# Shield.net
KiCad netlist of a schematic drawn in EAGLE
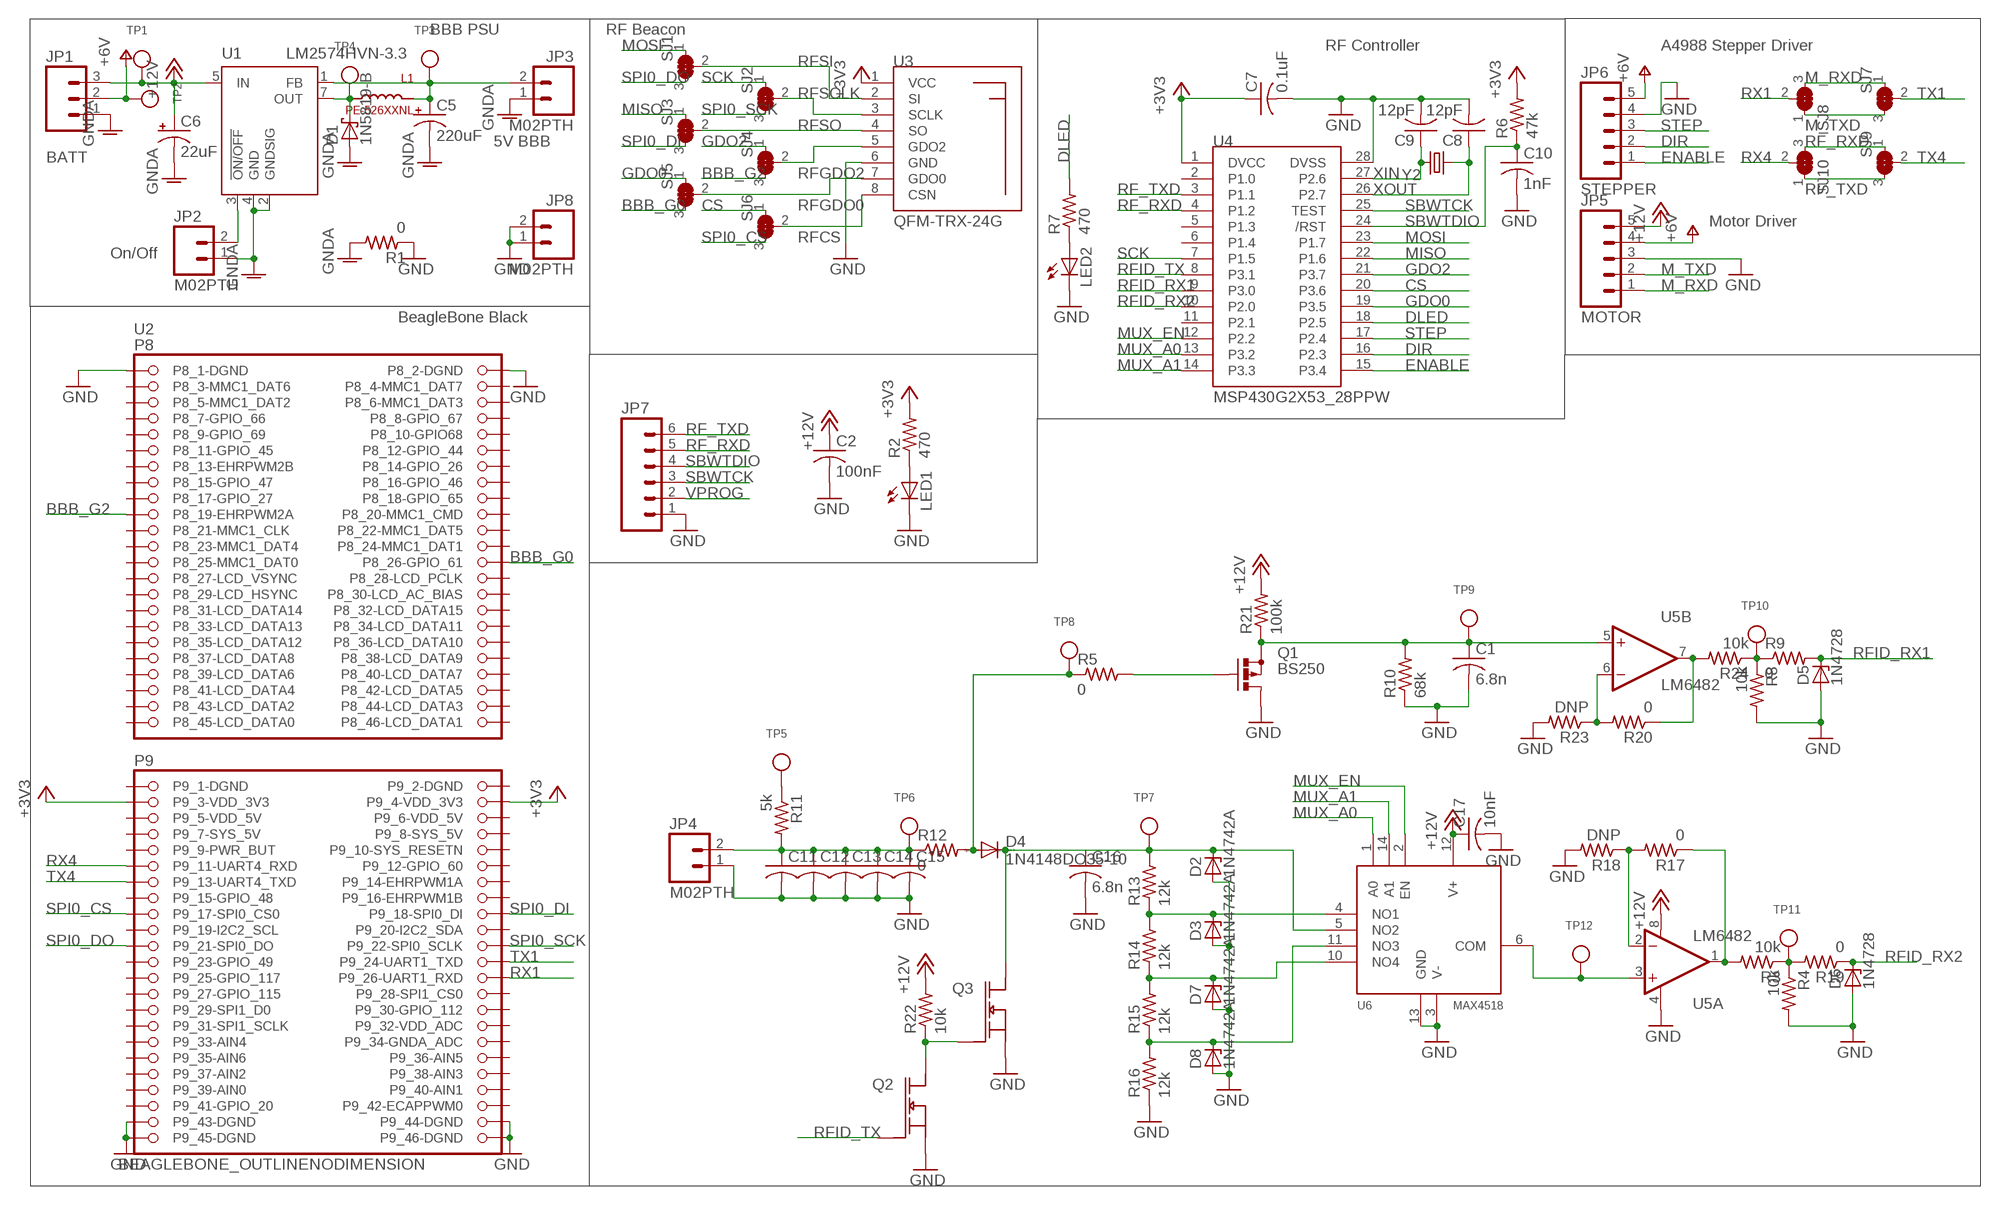
[diagram p0: schematic, sheet 1]

(export (version "E")
  (design (tool "Eeschema 10.0.6"))
  (components
    (comp (ref "C1")
      (value "6.8n")
      (footprint "eagle-import:C0805")
      (libsource (lib "eagle-import") (part "C-USC0805"))
    )
    (comp (ref "C2")
      (value "100nF")
      (footprint "eagle-import:C0805")
      (libsource (lib "eagle-import") (part "C-USC0805"))
    )
    (comp (ref "C5")
      (value "220uF")
      (footprint "eagle-import:E3,5-8")
      (libsource (lib "eagle-import") (part "CPOL-USE3.5-8"))
    )
    (comp (ref "C6")
      (value "22uF")
      (footprint "eagle-import:E2,5-5")
      (libsource (lib "eagle-import") (part "CPOL-USE2.5-5"))
    )
    (comp (ref "C7")
      (value "0.1uF")
      (footprint "eagle-import:C0805")
      (libsource (lib "eagle-import") (part "C-USC0805"))
    )
    (comp (ref "C8")
      (value "12pF")
      (footprint "eagle-import:C0805")
      (libsource (lib "eagle-import") (part "C-USC0805"))
    )
    (comp (ref "C9")
      (value "12pF")
      (footprint "eagle-import:C0805")
      (libsource (lib "eagle-import") (part "C-USC0805"))
    )
    (comp (ref "C10")
      (value "1nF")
      (footprint "eagle-import:C0805")
      (libsource (lib "eagle-import") (part "C-USC0805"))
    )
    (comp (ref "C11")
      (value "C-USC0805")
      (footprint "eagle-import:C0805")
      (libsource (lib "eagle-import") (part "C-USC0805"))
    )
    (comp (ref "C12")
      (value "C-USC0805")
      (footprint "eagle-import:C0805")
      (libsource (lib "eagle-import") (part "C-USC0805"))
    )
    (comp (ref "C13")
      (value "C-USC0805")
      (footprint "eagle-import:C0805")
      (libsource (lib "eagle-import") (part "C-USC0805"))
    )
    (comp (ref "C14")
      (value "C-USC0805")
      (footprint "eagle-import:C0805")
      (libsource (lib "eagle-import") (part "C-USC0805"))
    )
    (comp (ref "C15")
      (value "C-USC0805")
      (footprint "eagle-import:C0805")
      (libsource (lib "eagle-import") (part "C-USC0805"))
    )
    (comp (ref "C16")
      (value "6.8n")
      (footprint "eagle-import:C0805")
      (libsource (lib "eagle-import") (part "C-USC0805"))
    )
    (comp (ref "C17")
      (value "10nF")
      (footprint "eagle-import:C0805")
      (libsource (lib "eagle-import") (part "C-USC0805"))
    )
    (comp (ref "D1")
      (value "1N5819-B")
      (footprint "eagle-import:DO41-7.6")
      (libsource (lib "eagle-import") (part "1N5819-B"))
    )
    (comp (ref "D2")
      (value "1N4742A")
      (footprint "eagle-import:DO41Z10")
      (libsource (lib "eagle-import") (part "1N4728"))
    )
    (comp (ref "D3")
      (value "1N4742A")
      (footprint "eagle-import:DO41Z10")
      (libsource (lib "eagle-import") (part "1N4728"))
    )
    (comp (ref "D4")
      (value "1N4148DO35-10")
      (footprint "eagle-import:DO35-10")
      (libsource (lib "eagle-import") (part "1N4148DO35-10"))
    )
    (comp (ref "D5")
      (value "1N4728")
      (footprint "eagle-import:DO41Z10")
      (libsource (lib "eagle-import") (part "1N4728"))
    )
    (comp (ref "D6")
      (value "1N4728")
      (footprint "eagle-import:DO41Z10")
      (libsource (lib "eagle-import") (part "1N4728"))
    )
    (comp (ref "D7")
      (value "1N4742A")
      (footprint "eagle-import:DO41Z10")
      (libsource (lib "eagle-import") (part "1N4728"))
    )
    (comp (ref "D8")
      (value "1N4742A")
      (footprint "eagle-import:DO41Z10")
      (libsource (lib "eagle-import") (part "1N4728"))
    )
    (comp (ref "JP1")
      (value "M03PTH")
      (footprint "eagle-import:1X03")
      (libsource (lib "eagle-import") (part "M03PTH"))
    )
    (comp (ref "JP2")
      (value "M02PTH")
      (footprint "eagle-import:1X02")
      (libsource (lib "eagle-import") (part "M02PTH"))
    )
    (comp (ref "JP3")
      (value "M02PTH")
      (footprint "eagle-import:1X02")
      (libsource (lib "eagle-import") (part "M02PTH"))
    )
    (comp (ref "JP4")
      (value "M02PTH")
      (footprint "eagle-import:1X02")
      (libsource (lib "eagle-import") (part "M02PTH"))
    )
    (comp (ref "JP5")
      (value "MOTOR")
      (footprint "eagle-import:1X05")
      (libsource (lib "eagle-import") (part "M05PTH"))
    )
    (comp (ref "JP6")
      (value "STEPPER")
      (footprint "eagle-import:1X05")
      (libsource (lib "eagle-import") (part "M05PTH"))
    )
    (comp (ref "JP7")
      (value "M06SIP")
      (footprint "eagle-import:1X06")
      (libsource (lib "eagle-import") (part "M06SIP"))
    )
    (comp (ref "JP8")
      (value "M02PTH")
      (footprint "eagle-import:1X02")
      (libsource (lib "eagle-import") (part "M02PTH"))
    )
    (comp (ref "L1")
      (value "PE-526XXNL")
      (footprint "eagle-import:PE_VERTICAL")
      (libsource (lib "eagle-import") (part "PE-526XXNL"))
    )
    (comp (ref "LED1")
      (value "LEDCHIP-LED0805")
      (footprint "eagle-import:CHIP-LED0805")
      (libsource (lib "eagle-import") (part "LEDCHIP-LED0805"))
    )
    (comp (ref "LED2")
      (value "LEDCHIP-LED0805")
      (footprint "eagle-import:CHIP-LED0805")
      (libsource (lib "eagle-import") (part "LEDCHIP-LED0805"))
    )
    (comp (ref "Q1")
      (value "BS250")
      (footprint "eagle-import:SOT54E")
      (libsource (lib "eagle-import") (part "BS250"))
    )
    (comp (ref "Q2")
      (value "2N7002_SINGLESOT23/TO-236AB")
      (footprint "eagle-import:TO-236AB")
      (libsource (lib "eagle-import") (part "2N7002_SINGLESOT23/TO-236AB"))
    )
    (comp (ref "Q3")
      (value "2N7002_SINGLESOT23/TO-236AB")
      (footprint "eagle-import:TO-236AB")
      (libsource (lib "eagle-import") (part "2N7002_SINGLESOT23/TO-236AB"))
    )
    (comp (ref "R1")
      (value "0")
      (footprint "eagle-import:R0805")
      (libsource (lib "eagle-import") (part "R-US_R0805"))
    )
    (comp (ref "R2")
      (value "470")
      (footprint "eagle-import:R0805")
      (libsource (lib "eagle-import") (part "R-US_R0805"))
    )
    (comp (ref "R3")
      (value "10k")
      (footprint "eagle-import:R0805")
      (libsource (lib "eagle-import") (part "R-US_R0805"))
    )
    (comp (ref "R4")
      (value "10k")
      (footprint "eagle-import:R0805")
      (libsource (lib "eagle-import") (part "R-US_R0805"))
    )
    (comp (ref "R5")
      (value "0")
      (footprint "eagle-import:R0805")
      (libsource (lib "eagle-import") (part "R-US_R0805"))
    )
    (comp (ref "R6")
      (value "47k")
      (footprint "eagle-import:R0805")
      (libsource (lib "eagle-import") (part "R-US_R0805"))
    )
    (comp (ref "R7")
      (value "470")
      (footprint "eagle-import:R0805")
      (libsource (lib "eagle-import") (part "R-US_R0805"))
    )
    (comp (ref "R8")
      (value "10k")
      (footprint "eagle-import:R0805")
      (libsource (lib "eagle-import") (part "R-US_R0805"))
    )
    (comp (ref "R9")
      (value "0")
      (footprint "eagle-import:R0805")
      (libsource (lib "eagle-import") (part "R-US_R0805"))
    )
    (comp (ref "R10")
      (value "68k")
      (footprint "eagle-import:R0805")
      (libsource (lib "eagle-import") (part "R-US_R0805"))
    )
    (comp (ref "R11")
      (value "5k")
      (footprint "eagle-import:R0805")
      (libsource (lib "eagle-import") (part "R-US_R0805"))
    )
    (comp (ref "R12")
      (value "0")
      (footprint "eagle-import:R0805")
      (libsource (lib "eagle-import") (part "R-US_R0805"))
    )
    (comp (ref "R13")
      (value "12k")
      (footprint "eagle-import:R0805")
      (libsource (lib "eagle-import") (part "R-US_R0805"))
    )
    (comp (ref "R14")
      (value "12k")
      (footprint "eagle-import:R0805")
      (libsource (lib "eagle-import") (part "R-US_R0805"))
    )
    (comp (ref "R15")
      (value "12k")
      (footprint "eagle-import:R0805")
      (libsource (lib "eagle-import") (part "R-US_R0805"))
    )
    (comp (ref "R16")
      (value "12k")
      (footprint "eagle-import:R0805")
      (libsource (lib "eagle-import") (part "R-US_R0805"))
    )
    (comp (ref "R17")
      (value "0")
      (footprint "eagle-import:R0805")
      (libsource (lib "eagle-import") (part "R-US_R0805"))
    )
    (comp (ref "R18")
      (value "DNP")
      (footprint "eagle-import:R0805")
      (libsource (lib "eagle-import") (part "R-US_R0805"))
    )
    (comp (ref "R19")
      (value "0")
      (footprint "eagle-import:R0805")
      (libsource (lib "eagle-import") (part "R-US_R0805"))
    )
    (comp (ref "R20")
      (value "0")
      (footprint "eagle-import:R0805")
      (libsource (lib "eagle-import") (part "R-US_R0805"))
    )
    (comp (ref "R21")
      (value "100k")
      (footprint "eagle-import:R0805")
      (libsource (lib "eagle-import") (part "R-US_R0805"))
    )
    (comp (ref "R22")
      (value "10k")
      (footprint "eagle-import:R0805")
      (libsource (lib "eagle-import") (part "R-US_R0805"))
    )
    (comp (ref "R23")
      (value "DNP")
      (footprint "eagle-import:R0805")
      (libsource (lib "eagle-import") (part "R-US_R0805"))
    )
    (comp (ref "R24")
      (value "10k")
      (footprint "eagle-import:R0805")
      (libsource (lib "eagle-import") (part "R-US_R0805"))
    )
    (comp (ref "SJ1")
      (value "SOLDERJUMPER_2WAY0805")
      (footprint "eagle-import:SOLDERJUMPER_2WAY_OPEN_0805")
      (libsource (lib "eagle-import") (part "SOLDERJUMPER_2WAY0805"))
    )
    (comp (ref "SJ2")
      (value "SOLDERJUMPER_2WAY0805")
      (footprint "eagle-import:SOLDERJUMPER_2WAY_OPEN_0805")
      (libsource (lib "eagle-import") (part "SOLDERJUMPER_2WAY0805"))
    )
    (comp (ref "SJ3")
      (value "SOLDERJUMPER_2WAY0805")
      (footprint "eagle-import:SOLDERJUMPER_2WAY_OPEN_0805")
      (libsource (lib "eagle-import") (part "SOLDERJUMPER_2WAY0805"))
    )
    (comp (ref "SJ4")
      (value "SOLDERJUMPER_2WAY0805")
      (footprint "eagle-import:SOLDERJUMPER_2WAY_OPEN_0805")
      (libsource (lib "eagle-import") (part "SOLDERJUMPER_2WAY0805"))
    )
    (comp (ref "SJ5")
      (value "SOLDERJUMPER_2WAY0805")
      (footprint "eagle-import:SOLDERJUMPER_2WAY_OPEN_0805")
      (libsource (lib "eagle-import") (part "SOLDERJUMPER_2WAY0805"))
    )
    (comp (ref "SJ6")
      (value "SOLDERJUMPER_2WAY0805")
      (footprint "eagle-import:SOLDERJUMPER_2WAY_OPEN_0805")
      (libsource (lib "eagle-import") (part "SOLDERJUMPER_2WAY0805"))
    )
    (comp (ref "SJ7")
      (value "SOLDERJUMPER_2WAY0805")
      (footprint "eagle-import:SOLDERJUMPER_2WAY_OPEN_0805")
      (libsource (lib "eagle-import") (part "SOLDERJUMPER_2WAY0805"))
    )
    (comp (ref "SJ8")
      (value "SOLDERJUMPER_2WAY0805")
      (footprint "eagle-import:SOLDERJUMPER_2WAY_OPEN_0805")
      (libsource (lib "eagle-import") (part "SOLDERJUMPER_2WAY0805"))
    )
    (comp (ref "SJ9")
      (value "SOLDERJUMPER_2WAY0805")
      (footprint "eagle-import:SOLDERJUMPER_2WAY_OPEN_0805")
      (libsource (lib "eagle-import") (part "SOLDERJUMPER_2WAY0805"))
    )
    (comp (ref "SJ10")
      (value "SOLDERJUMPER_2WAY0805")
      (footprint "eagle-import:SOLDERJUMPER_2WAY_OPEN_0805")
      (libsource (lib "eagle-import") (part "SOLDERJUMPER_2WAY0805"))
    )
    (comp (ref "TP1")
      (value "TESTPOINT0.1\"")
      (footprint "eagle-import:1X01_ROUND")
      (libsource (lib "eagle-import") (part "TESTPOINT0.1{dblquote}"))
    )
    (comp (ref "TP2")
      (value "TESTPOINT0.1\"")
      (footprint "eagle-import:1X01_ROUND")
      (libsource (lib "eagle-import") (part "TESTPOINT0.1{dblquote}"))
    )
    (comp (ref "TP3")
      (value "TESTPOINT0.1\"")
      (footprint "eagle-import:1X01_ROUND")
      (libsource (lib "eagle-import") (part "TESTPOINT0.1{dblquote}"))
    )
    (comp (ref "TP4")
      (value "TESTPOINT0.1\"")
      (footprint "eagle-import:1X01_ROUND")
      (libsource (lib "eagle-import") (part "TESTPOINT0.1{dblquote}"))
    )
    (comp (ref "TP5")
      (value "TESTPOINT0.1\"")
      (footprint "eagle-import:1X01_ROUND")
      (libsource (lib "eagle-import") (part "TESTPOINT0.1{dblquote}"))
    )
    (comp (ref "TP6")
      (value "TESTPOINT0.1\"")
      (footprint "eagle-import:1X01_ROUND")
      (libsource (lib "eagle-import") (part "TESTPOINT0.1{dblquote}"))
    )
    (comp (ref "TP7")
      (value "TESTPOINT0.1\"")
      (footprint "eagle-import:1X01_ROUND")
      (libsource (lib "eagle-import") (part "TESTPOINT0.1{dblquote}"))
    )
    (comp (ref "TP8")
      (value "TESTPOINT0.1\"")
      (footprint "eagle-import:1X01_ROUND")
      (libsource (lib "eagle-import") (part "TESTPOINT0.1{dblquote}"))
    )
    (comp (ref "TP9")
      (value "TESTPOINT0.1\"")
      (footprint "eagle-import:1X01_ROUND")
      (libsource (lib "eagle-import") (part "TESTPOINT0.1{dblquote}"))
    )
    (comp (ref "TP10")
      (value "TESTPOINT0.1\"")
      (footprint "eagle-import:1X01_ROUND")
      (libsource (lib "eagle-import") (part "TESTPOINT0.1{dblquote}"))
    )
    (comp (ref "TP11")
      (value "TESTPOINT0.1\"")
      (footprint "eagle-import:1X01_ROUND")
      (libsource (lib "eagle-import") (part "TESTPOINT0.1{dblquote}"))
    )
    (comp (ref "TP12")
      (value "TESTPOINT0.1\"")
      (footprint "eagle-import:1X01_ROUND")
      (libsource (lib "eagle-import") (part "TESTPOINT0.1{dblquote}"))
    )
    (comp (ref "U1")
      (value "LM2574HVN-3.3")
      (footprint "eagle-import:DIL08")
      (libsource (lib "eagle-import") (part "LM2574?-HVN3.3"))
    )
    (comp (ref "U2")
      (value "BEAGLEBONE_OUTLINENODIMENSION")
      (footprint "eagle-import:BEAGLEBONE_SHIELD_NODIMENSION")
      (libsource (lib "eagle-import") (part "BEAGLEBONE_OUTLINENODIMENSION"))
    )
    (comp (ref "U3")
      (value "QFM-TRX-24G")
      (footprint "eagle-import:QFM-TRX1-24G")
      (libsource (lib "eagle-import") (part "QFM-TRX-24G"))
    )
    (comp (ref "U4")
      (value "MSP430G2X53_28PPW")
      (footprint "eagle-import:PW(R-PDSO-G28)")
      (libsource (lib "eagle-import") (part "MSP430G2X53_28PPW"))
    )
    (comp (ref "U5")
      (value "LM6482")
      (footprint "eagle-import:SOIC8")
      (libsource (lib "eagle-import") (part "LM6482"))
    )
    (comp (ref "U6")
      (value "MAX4518")
      (footprint "eagle-import:SO-14")
      (libsource (lib "eagle-import") (part "MAX4518"))
    )
    (comp (ref "Y2")
      (value "CRYSTALHC49UV")
      (footprint "eagle-import:HC49U-V")
      (libsource (lib "eagle-import") (part "CRYSTALHC49UV"))
    )
  )
  (nets
    (net (code "1") (name "+3V3") (class "Default")
      (node (ref "C7") (pin "1") (pinfunction "1_1") (pintype "passive"))
      (node (ref "R2") (pin "2") (pinfunction "2_2") (pintype "passive"))
      (node (ref "R6") (pin "2") (pinfunction "2_2") (pintype "passive"))
      (node (ref "U2") (pin "9.3") (pinfunction "P9_3-VDD_3V3_9.3") (pintype "power_in"))
      (node (ref "U2") (pin "9.4") (pinfunction "P9_4-VDD_3V3_9.4") (pintype "power_in"))
      (node (ref "U3") (pin "1") (pinfunction "VCC_1") (pintype "bidirectional"))
      (node (ref "U4") (pin "1") (pinfunction "DVCC_1") (pintype "bidirectional"))
    )
    (net (code "2") (name "+6V") (class "Default")
      (node (ref "JP1") (pin "2") (pinfunction "2_2") (pintype "passive"))
      (node (ref "JP5") (pin "4") (pinfunction "4_4") (pintype "passive"))
      (node (ref "JP6") (pin "5") (pinfunction "5_5") (pintype "passive"))
      (node (ref "TP2") (pin "1") (pinfunction "P$1_1") (pintype "bidirectional"))
    )
    (net (code "3") (name "+12V") (class "Default")
      (node (ref "C17") (pin "1") (pinfunction "1_1") (pintype "passive"))
      (node (ref "C2") (pin "1") (pinfunction "1_1") (pintype "passive"))
      (node (ref "C6") (pin "+") (pinfunction "+_+") (pintype "passive"))
      (node (ref "JP1") (pin "3") (pinfunction "3_3") (pintype "passive"))
      (node (ref "JP5") (pin "5") (pinfunction "5_5") (pintype "passive"))
      (node (ref "R21") (pin "2") (pinfunction "2_2") (pintype "passive"))
      (node (ref "R22") (pin "2") (pinfunction "2_2") (pintype "passive"))
      (node (ref "TP1") (pin "1") (pinfunction "P$1_1") (pintype "bidirectional"))
      (node (ref "U1") (pin "5") (pinfunction "IN_5") (pintype "input"))
      (node (ref "U5") (pin "8") (pinfunction "V+_8") (pintype "power_in"))
      (node (ref "U6") (pin "12") (pinfunction "V+_12") (pintype "bidirectional"))
    )
    (net (code "4") (name "/BBB_G0") (class "Default")
      (node (ref "SJ5") (pin "3") (pinfunction "3_3") (pintype "passive"))
      (node (ref "U2") (pin "8.26") (pinfunction "P8_26-GPIO_61_8.26") (pintype "passive"))
    )
    (net (code "5") (name "/BBB_G2") (class "Default")
      (node (ref "SJ4") (pin "3") (pinfunction "3_3") (pintype "passive"))
      (node (ref "U2") (pin "8.19") (pinfunction "P8_19-EHRPWM2A_8.19") (pintype "passive"))
    )
    (net (code "6") (name "/CS") (class "Default")
      (node (ref "SJ6") (pin "1") (pinfunction "1_1") (pintype "passive"))
      (node (ref "U4") (pin "20") (pinfunction "P3.6_20") (pintype "bidirectional"))
    )
    (net (code "7") (name "/DIR") (class "Default")
      (node (ref "JP6") (pin "2") (pinfunction "2_2") (pintype "passive"))
      (node (ref "U4") (pin "16") (pinfunction "P2.3_16") (pintype "bidirectional"))
    )
    (net (code "8") (name "/DLED") (class "Default")
      (node (ref "R7") (pin "2") (pinfunction "2_2") (pintype "passive"))
      (node (ref "U4") (pin "18") (pinfunction "P2.5_18") (pintype "bidirectional"))
    )
    (net (code "9") (name "/ENABLE") (class "Default")
      (node (ref "JP6") (pin "1") (pinfunction "1_1") (pintype "passive"))
      (node (ref "U4") (pin "15") (pinfunction "P3.4_15") (pintype "bidirectional"))
    )
    (net (code "10") (name "/GDO0") (class "Default")
      (node (ref "SJ5") (pin "1") (pinfunction "1_1") (pintype "passive"))
      (node (ref "U4") (pin "19") (pinfunction "P3.5_19") (pintype "bidirectional"))
    )
    (net (code "11") (name "/GDO2") (class "Default")
      (node (ref "SJ4") (pin "1") (pinfunction "1_1") (pintype "passive"))
      (node (ref "U4") (pin "21") (pinfunction "P3.7_21") (pintype "bidirectional"))
    )
    (net (code "12") (name "/MISO") (class "Default")
      (node (ref "SJ3") (pin "1") (pinfunction "1_1") (pintype "passive"))
      (node (ref "U4") (pin "22") (pinfunction "P1.6_22") (pintype "bidirectional"))
    )
    (net (code "13") (name "/MOSI") (class "Default")
      (node (ref "SJ1") (pin "1") (pinfunction "1_1") (pintype "passive"))
      (node (ref "U4") (pin "23") (pinfunction "P1.7_23") (pintype "bidirectional"))
    )
    (net (code "14") (name "/MUX_A0") (class "Default")
      (node (ref "U4") (pin "13") (pinfunction "P3.2_13") (pintype "bidirectional"))
      (node (ref "U6") (pin "1") (pinfunction "A0_1") (pintype "bidirectional"))
    )
    (net (code "15") (name "/MUX_A1") (class "Default")
      (node (ref "U4") (pin "14") (pinfunction "P3.3_14") (pintype "bidirectional"))
      (node (ref "U6") (pin "14") (pinfunction "A1_14") (pintype "bidirectional"))
    )
    (net (code "16") (name "/MUX_EN") (class "Default")
      (node (ref "U4") (pin "12") (pinfunction "P2.2_12") (pintype "bidirectional"))
      (node (ref "U6") (pin "2") (pinfunction "EN_2") (pintype "bidirectional"))
    )
    (net (code "17") (name "/M_RXD") (class "Default")
      (node (ref "JP5") (pin "1") (pinfunction "1_1") (pintype "passive"))
      (node (ref "SJ7") (pin "1") (pinfunction "1_1") (pintype "passive"))
      (node (ref "SJ8") (pin "3") (pinfunction "3_3") (pintype "passive"))
    )
    (net (code "18") (name "/M_TXD") (class "Default")
      (node (ref "JP5") (pin "2") (pinfunction "2_2") (pintype "passive"))
      (node (ref "SJ7") (pin "3") (pinfunction "3_3") (pintype "passive"))
      (node (ref "SJ8") (pin "1") (pinfunction "1_1") (pintype "passive"))
    )
    (net (code "19") (name "/P9_1-DGND") (class "Default")
      (node (ref "U2") (pin "9.1") (pinfunction "P9_1-DGND_9.1") (pintype "power_in"))
    )
    (net (code "20") (name "/P9_2-DGND") (class "Default")
      (node (ref "U2") (pin "9.2") (pinfunction "P9_2-DGND_9.2") (pintype "power_in"))
    )
    (net (code "21") (name "/P9_5-VDD_5V") (class "Default")
      (node (ref "U2") (pin "9.5") (pinfunction "P9_5-VDD_5V_9.5") (pintype "power_in"))
    )
    (net (code "22") (name "/P9_6-VDD_5V") (class "Default")
      (node (ref "U2") (pin "9.6") (pinfunction "P9_6-VDD_5V_9.6") (pintype "power_in"))
    )
    (net (code "23") (name "/P9_7-SYS_5V") (class "Default")
      (node (ref "U2") (pin "9.7") (pinfunction "P9_7-SYS_5V_9.7") (pintype "power_in"))
    )
    (net (code "24") (name "/P9_39-AIN0") (class "Default")
      (node (ref "U2") (pin "9.39") (pinfunction "P9_39-AIN0_9.39") (pintype "power_in"))
    )
    (net (code "25") (name "/RFCS") (class "Default")
      (node (ref "SJ6") (pin "2") (pinfunction "2_2") (pintype "passive"))
      (node (ref "U3") (pin "8") (pinfunction "CSN_8") (pintype "bidirectional"))
    )
    (net (code "26") (name "/RFGDO0") (class "Default")
      (node (ref "SJ5") (pin "2") (pinfunction "2_2") (pintype "passive"))
      (node (ref "U3") (pin "7") (pinfunction "GDO0_7") (pintype "bidirectional"))
    )
    (net (code "27") (name "/RFGDO2") (class "Default")
      (node (ref "SJ4") (pin "2") (pinfunction "2_2") (pintype "passive"))
      (node (ref "U3") (pin "5") (pinfunction "GDO2_5") (pintype "bidirectional"))
    )
    (net (code "28") (name "/RFID_RX1") (class "Default")
      (node (ref "D5") (pin "C") (pinfunction "C_C") (pintype "passive"))
      (node (ref "R9") (pin "2") (pinfunction "2_2") (pintype "passive"))
      (node (ref "U4") (pin "9") (pinfunction "P3.0_9") (pintype "bidirectional"))
    )
    (net (code "29") (name "/RFID_RX2") (class "Default")
      (node (ref "D6") (pin "C") (pinfunction "C_C") (pintype "passive"))
      (node (ref "R19") (pin "1") (pinfunction "1_1") (pintype "passive"))
      (node (ref "U4") (pin "10") (pinfunction "P2.0_10") (pintype "bidirectional"))
    )
    (net (code "30") (name "/RFID_TX") (class "Default")
      (node (ref "Q2") (pin "1") (pinfunction "G_1") (pintype "bidirectional"))
      (node (ref "U4") (pin "8") (pinfunction "P3.1_8") (pintype "bidirectional"))
    )
    (net (code "31") (name "/RFSCLK") (class "Default")
      (node (ref "SJ2") (pin "2") (pinfunction "2_2") (pintype "passive"))
      (node (ref "U3") (pin "3") (pinfunction "SCLK_3") (pintype "bidirectional"))
    )
    (net (code "32") (name "/RFSI") (class "Default")
      (node (ref "SJ1") (pin "2") (pinfunction "2_2") (pintype "passive"))
      (node (ref "U3") (pin "2") (pinfunction "SI_2") (pintype "bidirectional"))
    )
    (net (code "33") (name "/RFSO") (class "Default")
      (node (ref "SJ3") (pin "2") (pinfunction "2_2") (pintype "passive"))
      (node (ref "U3") (pin "4") (pinfunction "SO_4") (pintype "bidirectional"))
    )
    (net (code "34") (name "/RF_RXD") (class "Default")
      (node (ref "JP7") (pin "5") (pinfunction "5_5") (pintype "passive"))
      (node (ref "SJ10") (pin "3") (pinfunction "3_3") (pintype "passive"))
      (node (ref "SJ9") (pin "1") (pinfunction "1_1") (pintype "passive"))
      (node (ref "U4") (pin "4") (pinfunction "P1.2_4") (pintype "bidirectional"))
    )
    (net (code "35") (name "/RF_TXD") (class "Default")
      (node (ref "JP7") (pin "6") (pinfunction "6_6") (pintype "passive"))
      (node (ref "SJ10") (pin "1") (pinfunction "1_1") (pintype "passive"))
      (node (ref "SJ9") (pin "3") (pinfunction "3_3") (pintype "passive"))
      (node (ref "U4") (pin "3") (pinfunction "P1.1_3") (pintype "bidirectional"))
    )
    (net (code "36") (name "/RX1") (class "Default")
      (node (ref "SJ8") (pin "2") (pinfunction "2_2") (pintype "passive"))
      (node (ref "U2") (pin "9.26") (pinfunction "P9_26-UART1_RXD_9.26") (pintype "passive"))
    )
    (net (code "37") (name "/RX4") (class "Default")
      (node (ref "SJ10") (pin "2") (pinfunction "2_2") (pintype "passive"))
      (node (ref "U2") (pin "9.11") (pinfunction "P9_11-UART4_RXD_9.11") (pintype "passive"))
    )
    (net (code "38") (name "/SBWTCK") (class "Default")
      (node (ref "JP7") (pin "3") (pinfunction "3_3") (pintype "passive"))
      (node (ref "U4") (pin "25") (pinfunction "TEST_25") (pintype "bidirectional"))
    )
    (net (code "39") (name "/SBWTDIO") (class "Default")
      (node (ref "C10") (pin "1") (pinfunction "1_1") (pintype "passive"))
      (node (ref "JP7") (pin "4") (pinfunction "4_4") (pintype "passive"))
      (node (ref "R6") (pin "1") (pinfunction "1_1") (pintype "passive"))
      (node (ref "U4") (pin "24") (pinfunction "/RST_24") (pintype "bidirectional"))
    )
    (net (code "40") (name "/SCK") (class "Default")
      (node (ref "SJ2") (pin "1") (pinfunction "1_1") (pintype "passive"))
      (node (ref "U4") (pin "7") (pinfunction "P1.5_7") (pintype "bidirectional"))
    )
    (net (code "41") (name "/SPI0_CS") (class "Default")
      (node (ref "SJ6") (pin "3") (pinfunction "3_3") (pintype "passive"))
      (node (ref "U2") (pin "9.17") (pinfunction "P9_17-SPI0_CS0_9.17") (pintype "passive"))
    )
    (net (code "42") (name "/SPI0_DI") (class "Default")
      (node (ref "SJ3") (pin "3") (pinfunction "3_3") (pintype "passive"))
      (node (ref "U2") (pin "9.18") (pinfunction "P9_18-SPI0_DI_9.18") (pintype "passive"))
    )
    (net (code "43") (name "/SPI0_DO") (class "Default")
      (node (ref "SJ1") (pin "3") (pinfunction "3_3") (pintype "passive"))
      (node (ref "U2") (pin "9.21") (pinfunction "P9_21-SPI0_DO_9.21") (pintype "passive"))
    )
    (net (code "44") (name "/SPI0_SCK") (class "Default")
      (node (ref "SJ2") (pin "3") (pinfunction "3_3") (pintype "passive"))
      (node (ref "U2") (pin "9.22") (pinfunction "P9_22-SPI0_SCLK_9.22") (pintype "passive"))
    )
    (net (code "45") (name "/STEP") (class "Default")
      (node (ref "JP6") (pin "3") (pinfunction "3_3") (pintype "passive"))
      (node (ref "U4") (pin "17") (pinfunction "P2.4_17") (pintype "bidirectional"))
    )
    (net (code "46") (name "/TX1") (class "Default")
      (node (ref "SJ7") (pin "2") (pinfunction "2_2") (pintype "passive"))
      (node (ref "U2") (pin "9.24") (pinfunction "P9_24-UART1_TXD_9.24") (pintype "passive"))
    )
    (net (code "47") (name "/TX4") (class "Default")
      (node (ref "SJ9") (pin "2") (pinfunction "2_2") (pintype "passive"))
      (node (ref "U2") (pin "9.13") (pinfunction "P9_13-UART4_TXD_9.13") (pintype "passive"))
    )
    (net (code "48") (name "/VPROG") (class "Default")
      (node (ref "JP7") (pin "2") (pinfunction "2_2") (pintype "passive"))
    )
    (net (code "49") (name "/XIN") (class "Default")
      (node (ref "C9") (pin "1") (pinfunction "1_1") (pintype "passive"))
      (node (ref "U4") (pin "27") (pinfunction "P2.6_27") (pintype "bidirectional"))
      (node (ref "Y2") (pin "2") (pinfunction "2_2") (pintype "passive"))
    )
    (net (code "50") (name "/XOUT") (class "Default")
      (node (ref "C8") (pin "1") (pinfunction "1_1") (pintype "passive"))
      (node (ref "U4") (pin "26") (pinfunction "P2.7_26") (pintype "bidirectional"))
      (node (ref "Y2") (pin "1") (pinfunction "1_1") (pintype "passive"))
    )
    (net (code "51") (name "GND") (class "Default")
      (node (ref "C1") (pin "2") (pinfunction "2_2") (pintype "passive"))
      (node (ref "C10") (pin "2") (pinfunction "2_2") (pintype "passive"))
      (node (ref "C11") (pin "2") (pinfunction "2_2") (pintype "passive"))
      (node (ref "C12") (pin "2") (pinfunction "2_2") (pintype "passive"))
      (node (ref "C13") (pin "2") (pinfunction "2_2") (pintype "passive"))
      (node (ref "C14") (pin "2") (pinfunction "2_2") (pintype "passive"))
      (node (ref "C15") (pin "2") (pinfunction "2_2") (pintype "passive"))
      (node (ref "C16") (pin "2") (pinfunction "2_2") (pintype "passive"))
      (node (ref "C17") (pin "2") (pinfunction "2_2") (pintype "passive"))
      (node (ref "C2") (pin "2") (pinfunction "2_2") (pintype "passive"))
      (node (ref "C7") (pin "2") (pinfunction "2_2") (pintype "passive"))
      (node (ref "C8") (pin "2") (pinfunction "2_2") (pintype "passive"))
      (node (ref "C9") (pin "2") (pinfunction "2_2") (pintype "passive"))
      (node (ref "D2") (pin "A") (pinfunction "A_A") (pintype "passive"))
      (node (ref "D3") (pin "A") (pinfunction "A_A") (pintype "passive"))
      (node (ref "D5") (pin "A") (pinfunction "A_A") (pintype "passive"))
      (node (ref "D6") (pin "A") (pinfunction "A_A") (pintype "passive"))
      (node (ref "D7") (pin "A") (pinfunction "A_A") (pintype "passive"))
      (node (ref "D8") (pin "A") (pinfunction "A_A") (pintype "passive"))
      (node (ref "JP4") (pin "1") (pinfunction "1_1") (pintype "passive"))
      (node (ref "JP5") (pin "3") (pinfunction "3_3") (pintype "passive"))
      (node (ref "JP6") (pin "4") (pinfunction "4_4") (pintype "passive"))
      (node (ref "JP7") (pin "1") (pinfunction "1_1") (pintype "passive"))
      (node (ref "JP8") (pin "1") (pinfunction "1_1") (pintype "passive"))
      (node (ref "JP8") (pin "2") (pinfunction "2_2") (pintype "passive"))
      (node (ref "LED1") (pin "C") (pinfunction "C_C") (pintype "passive"))
      (node (ref "LED2") (pin "C") (pinfunction "C_C") (pintype "passive"))
      (node (ref "Q1") (pin "D") (pinfunction "D_D") (pintype "passive"))
      (node (ref "Q2") (pin "2") (pinfunction "S_2") (pintype "bidirectional"))
      (node (ref "Q3") (pin "2") (pinfunction "S_2") (pintype "bidirectional"))
      (node (ref "R1") (pin "1") (pinfunction "1_1") (pintype "passive"))
      (node (ref "R10") (pin "1") (pinfunction "1_1") (pintype "passive"))
      (node (ref "R16") (pin "1") (pinfunction "1_1") (pintype "passive"))
      (node (ref "R18") (pin "2") (pinfunction "2_2") (pintype "passive"))
      (node (ref "R23") (pin "2") (pinfunction "2_2") (pintype "passive"))
      (node (ref "R4") (pin "2") (pinfunction "2_2") (pintype "passive"))
      (node (ref "R8") (pin "2") (pinfunction "2_2") (pintype "passive"))
      (node (ref "U2") (pin "8.1") (pinfunction "P8_1-DGND_8.1") (pintype "power_in"))
      (node (ref "U2") (pin "8.2") (pinfunction "P8_2-DGND_8.2") (pintype "power_in"))
      (node (ref "U2") (pin "9.43") (pinfunction "P9_43-DGND_9.43") (pintype "power_in"))
      (node (ref "U2") (pin "9.44") (pinfunction "P9_44-DGND_9.44") (pintype "power_in"))
      (node (ref "U2") (pin "9.45") (pinfunction "P9_45-DGND_9.45") (pintype "power_in"))
      (node (ref "U2") (pin "9.46") (pinfunction "P9_46-DGND_9.46") (pintype "power_in"))
      (node (ref "U3") (pin "6") (pinfunction "GND_6") (pintype "bidirectional"))
      (node (ref "U4") (pin "28") (pinfunction "DVSS_28") (pintype "bidirectional"))
      (node (ref "U5") (pin "4") (pinfunction "V-_4") (pintype "power_in"))
      (node (ref "U6") (pin "13") (pinfunction "GND_13") (pintype "bidirectional"))
      (node (ref "U6") (pin "3") (pinfunction "V-_3") (pintype "bidirectional"))
    )
    (net (code "52") (name "GNDA") (class "Default")
      (node (ref "C5") (pin "-") (pinfunction "-_-") (pintype "passive"))
      (node (ref "C6") (pin "-") (pinfunction "-_-") (pintype "passive"))
      (node (ref "D1") (pin "A") (pinfunction "A_A") (pintype "passive"))
      (node (ref "JP1") (pin "1") (pinfunction "1_1") (pintype "passive"))
      (node (ref "JP2") (pin "1") (pinfunction "1_1") (pintype "passive"))
      (node (ref "JP3") (pin "1") (pinfunction "1_1") (pintype "passive"))
      (node (ref "R1") (pin "2") (pinfunction "2_2") (pintype "passive"))
      (node (ref "U1") (pin "2") (pinfunction "GNDSIG_2") (pintype "input"))
      (node (ref "U1") (pin "4") (pinfunction "GND_4") (pintype "power_in"))
    )
    (net (code "53") (name "Net-(L1-P$1)") (class "Default")
      (node (ref "C5") (pin "+") (pinfunction "+_+") (pintype "passive"))
      (node (ref "JP3") (pin "2") (pinfunction "2_2") (pintype "passive"))
      (node (ref "L1") (pin "1") (pinfunction "P$1_1") (pintype "bidirectional"))
      (node (ref "TP3") (pin "1") (pinfunction "P$1_1") (pintype "bidirectional"))
      (node (ref "U1") (pin "1") (pinfunction "FB_1") (pintype "input"))
    )
    (net (code "54") (name "Net-(L1-P$2)") (class "Default")
      (node (ref "D1") (pin "C") (pinfunction "C_C") (pintype "passive"))
      (node (ref "L1") (pin "2") (pinfunction "P$2_2") (pintype "bidirectional"))
      (node (ref "TP4") (pin "1") (pinfunction "P$1_1") (pintype "bidirectional"))
      (node (ref "U1") (pin "7") (pinfunction "OUT_7") (pintype "passive"))
    )
    (net (code "55") (name "Net-(LED1-PadA)") (class "Default")
      (node (ref "LED1") (pin "A") (pinfunction "A_A") (pintype "passive"))
      (node (ref "R2") (pin "1") (pinfunction "1_1") (pintype "passive"))
    )
    (net (code "56") (name "Net-(LED2-PadA)") (class "Default")
      (node (ref "LED2") (pin "A") (pinfunction "A_A") (pintype "passive"))
      (node (ref "R7") (pin "1") (pinfunction "1_1") (pintype "passive"))
    )
    (net (code "57") (name "Net-(Q1-PadG)") (class "Default")
      (node (ref "Q1") (pin "G") (pinfunction "G_G") (pintype "passive"))
      (node (ref "R5") (pin "2") (pinfunction "2_2") (pintype "passive"))
    )
    (net (code "58") (name "Net-(Q2-D)") (class "Default")
      (node (ref "Q2") (pin "3") (pinfunction "D_3") (pintype "bidirectional"))
      (node (ref "Q3") (pin "1") (pinfunction "G_1") (pintype "bidirectional"))
      (node (ref "R22") (pin "1") (pinfunction "1_1") (pintype "passive"))
    )
    (net (code "59") (name "Net-(Q3-D)") (class "Default")
      (node (ref "C16") (pin "1") (pinfunction "1_1") (pintype "passive"))
      (node (ref "D2") (pin "C") (pinfunction "C_C") (pintype "passive"))
      (node (ref "D4") (pin "C") (pinfunction "C_C") (pintype "passive"))
      (node (ref "Q3") (pin "3") (pinfunction "D_3") (pintype "bidirectional"))
      (node (ref "R13") (pin "2") (pinfunction "2_2") (pintype "passive"))
      (node (ref "TP7") (pin "1") (pinfunction "P$1_1") (pintype "bidirectional"))
      (node (ref "U6") (pin "5") (pinfunction "NO2_5") (pintype "bidirectional"))
    )
    (net (code "60") (name "Net-(TP5-P$1)") (class "Default")
      (node (ref "R11") (pin "1") (pinfunction "1_1") (pintype "passive"))
      (node (ref "TP5") (pin "1") (pinfunction "P$1_1") (pintype "bidirectional"))
    )
    (net (code "61") (name "Net-(TP6-P$1)") (class "Default")
      (node (ref "C11") (pin "1") (pinfunction "1_1") (pintype "passive"))
      (node (ref "C12") (pin "1") (pinfunction "1_1") (pintype "passive"))
      (node (ref "C13") (pin "1") (pinfunction "1_1") (pintype "passive"))
      (node (ref "C14") (pin "1") (pinfunction "1_1") (pintype "passive"))
      (node (ref "C15") (pin "1") (pinfunction "1_1") (pintype "passive"))
      (node (ref "JP4") (pin "2") (pinfunction "2_2") (pintype "passive"))
      (node (ref "R11") (pin "2") (pinfunction "2_2") (pintype "passive"))
      (node (ref "R12") (pin "1") (pinfunction "1_1") (pintype "passive"))
      (node (ref "TP6") (pin "1") (pinfunction "P$1_1") (pintype "bidirectional"))
    )
    (net (code "62") (name "Net-(TP8-P$1)") (class "Default")
      (node (ref "D4") (pin "A") (pinfunction "A_A") (pintype "passive"))
      (node (ref "R12") (pin "2") (pinfunction "2_2") (pintype "passive"))
      (node (ref "R5") (pin "1") (pinfunction "1_1") (pintype "passive"))
      (node (ref "TP8") (pin "1") (pinfunction "P$1_1") (pintype "bidirectional"))
    )
    (net (code "63") (name "Net-(TP9-P$1)") (class "Default")
      (node (ref "C1") (pin "1") (pinfunction "1_1") (pintype "passive"))
      (node (ref "Q1") (pin "S") (pinfunction "S_S") (pintype "passive"))
      (node (ref "R10") (pin "2") (pinfunction "2_2") (pintype "passive"))
      (node (ref "R21") (pin "1") (pinfunction "1_1") (pintype "passive"))
      (node (ref "TP9") (pin "1") (pinfunction "P$1_1") (pintype "bidirectional"))
      (node (ref "U5") (pin "5") (pinfunction "+IN_5") (pintype "input"))
    )
    (net (code "64") (name "Net-(TP10-P$1)") (class "Default")
      (node (ref "R24") (pin "1") (pinfunction "1_1") (pintype "passive"))
      (node (ref "R8") (pin "1") (pinfunction "1_1") (pintype "passive"))
      (node (ref "R9") (pin "1") (pinfunction "1_1") (pintype "passive"))
      (node (ref "TP10") (pin "1") (pinfunction "P$1_1") (pintype "bidirectional"))
    )
    (net (code "65") (name "Net-(TP11-P$1)") (class "Default")
      (node (ref "R19") (pin "2") (pinfunction "2_2") (pintype "passive"))
      (node (ref "R3") (pin "1") (pinfunction "1_1") (pintype "passive"))
      (node (ref "R4") (pin "1") (pinfunction "1_1") (pintype "passive"))
      (node (ref "TP11") (pin "1") (pinfunction "P$1_1") (pintype "bidirectional"))
    )
    (net (code "66") (name "Net-(TP12-P$1)") (class "Default")
      (node (ref "TP12") (pin "1") (pinfunction "P$1_1") (pintype "bidirectional"))
      (node (ref "U5") (pin "3") (pinfunction "+IN_3") (pintype "input"))
      (node (ref "U6") (pin "6") (pinfunction "COM_6") (pintype "bidirectional"))
    )
    (net (code "67") (name "Net-(U1-~{ON{slash}OFF})") (class "Default")
      (node (ref "JP2") (pin "2") (pinfunction "2_2") (pintype "passive"))
      (node (ref "U1") (pin "3") (pinfunction "~{ON/OFF}_3") (pintype "input"))
    )
    (net (code "68") (name "Net-(U5A--IN)") (class "Default")
      (node (ref "R17") (pin "2") (pinfunction "2_2") (pintype "passive"))
      (node (ref "R18") (pin "1") (pinfunction "1_1") (pintype "passive"))
      (node (ref "U5") (pin "2") (pinfunction "-IN_2") (pintype "input"))
    )
    (net (code "69") (name "Net-(U5A-OUT)") (class "Default")
      (node (ref "R17") (pin "1") (pinfunction "1_1") (pintype "passive"))
      (node (ref "R3") (pin "2") (pinfunction "2_2") (pintype "passive"))
      (node (ref "U5") (pin "1") (pinfunction "OUT_1") (pintype "output"))
    )
    (net (code "70") (name "Net-(U5B--IN)") (class "Default")
      (node (ref "R20") (pin "2") (pinfunction "2_2") (pintype "passive"))
      (node (ref "R23") (pin "1") (pinfunction "1_1") (pintype "passive"))
      (node (ref "U5") (pin "6") (pinfunction "-IN_6") (pintype "input"))
    )
    (net (code "71") (name "Net-(U5B-OUT)") (class "Default")
      (node (ref "R20") (pin "1") (pinfunction "1_1") (pintype "passive"))
      (node (ref "R24") (pin "2") (pinfunction "2_2") (pintype "passive"))
      (node (ref "U5") (pin "7") (pinfunction "OUT_7") (pintype "output"))
    )
    (net (code "72") (name "Net-(U6-NO1)") (class "Default")
      (node (ref "D3") (pin "C") (pinfunction "C_C") (pintype "passive"))
      (node (ref "R13") (pin "1") (pinfunction "1_1") (pintype "passive"))
      (node (ref "R14") (pin "2") (pinfunction "2_2") (pintype "passive"))
      (node (ref "U6") (pin "4") (pinfunction "NO1_4") (pintype "bidirectional"))
    )
    (net (code "73") (name "Net-(U6-NO3)") (class "Default")
      (node (ref "D8") (pin "C") (pinfunction "C_C") (pintype "passive"))
      (node (ref "R15") (pin "1") (pinfunction "1_1") (pintype "passive"))
      (node (ref "R16") (pin "2") (pinfunction "2_2") (pintype "passive"))
      (node (ref "U6") (pin "11") (pinfunction "NO3_11") (pintype "bidirectional"))
    )
    (net (code "74") (name "Net-(U6-NO4)") (class "Default")
      (node (ref "D7") (pin "C") (pinfunction "C_C") (pintype "passive"))
      (node (ref "R14") (pin "1") (pinfunction "1_1") (pintype "passive"))
      (node (ref "R15") (pin "2") (pinfunction "2_2") (pintype "passive"))
      (node (ref "U6") (pin "10") (pinfunction "NO4_10") (pintype "bidirectional"))
    )
    (net (code "75") (name "unconnected-(U2-P8_3-MMC1_DAT6-Pad8.3)") (class "Default")
      (node (ref "U2") (pin "8.3") (pinfunction "P8_3-MMC1_DAT6_8.3") (pintype "passive"))
    )
    (net (code "76") (name "unconnected-(U2-P8_4-MMC1_DAT7-Pad8.4)") (class "Default")
      (node (ref "U2") (pin "8.4") (pinfunction "P8_4-MMC1_DAT7_8.4") (pintype "passive"))
    )
    (net (code "77") (name "unconnected-(U2-P8_5-MMC1_DAT2-Pad8.5)") (class "Default")
      (node (ref "U2") (pin "8.5") (pinfunction "P8_5-MMC1_DAT2_8.5") (pintype "passive"))
    )
    (net (code "78") (name "unconnected-(U2-P8_6-MMC1_DAT3-Pad8.6)") (class "Default")
      (node (ref "U2") (pin "8.6") (pinfunction "P8_6-MMC1_DAT3_8.6") (pintype "passive"))
    )
    (net (code "79") (name "unconnected-(U2-P8_7-GPIO_66-Pad8.7)") (class "Default")
      (node (ref "U2") (pin "8.7") (pinfunction "P8_7-GPIO_66_8.7") (pintype "passive"))
    )
    (net (code "80") (name "unconnected-(U2-P8_8-GPIO_67-Pad8.8)") (class "Default")
      (node (ref "U2") (pin "8.8") (pinfunction "P8_8-GPIO_67_8.8") (pintype "passive"))
    )
    (net (code "81") (name "unconnected-(U2-P8_9-GPIO_69-Pad8.9)") (class "Default")
      (node (ref "U2") (pin "8.9") (pinfunction "P8_9-GPIO_69_8.9") (pintype "passive"))
    )
    (net (code "82") (name "unconnected-(U2-P8_10-GPIO68-Pad8.10)") (class "Default")
      (node (ref "U2") (pin "8.10") (pinfunction "P8_10-GPIO68_8.10") (pintype "passive"))
    )
    (net (code "83") (name "unconnected-(U2-P8_11-GPIO_45-Pad8.11)") (class "Default")
      (node (ref "U2") (pin "8.11") (pinfunction "P8_11-GPIO_45_8.11") (pintype "passive"))
    )
    (net (code "84") (name "unconnected-(U2-P8_12-GPIO_44-Pad8.12)") (class "Default")
      (node (ref "U2") (pin "8.12") (pinfunction "P8_12-GPIO_44_8.12") (pintype "passive"))
    )
    (net (code "85") (name "unconnected-(U2-P8_13-EHRPWM2B-Pad8.13)") (class "Default")
      (node (ref "U2") (pin "8.13") (pinfunction "P8_13-EHRPWM2B_8.13") (pintype "passive"))
    )
    (net (code "86") (name "unconnected-(U2-P8_14-GPIO_26-Pad8.14)") (class "Default")
      (node (ref "U2") (pin "8.14") (pinfunction "P8_14-GPIO_26_8.14") (pintype "passive"))
    )
    (net (code "87") (name "unconnected-(U2-P8_15-GPIO_47-Pad8.15)") (class "Default")
      (node (ref "U2") (pin "8.15") (pinfunction "P8_15-GPIO_47_8.15") (pintype "passive"))
    )
    (net (code "88") (name "unconnected-(U2-P8_16-GPIO_46-Pad8.16)") (class "Default")
      (node (ref "U2") (pin "8.16") (pinfunction "P8_16-GPIO_46_8.16") (pintype "passive"))
    )
    (net (code "89") (name "unconnected-(U2-P8_17-GPIO_27-Pad8.17)") (class "Default")
      (node (ref "U2") (pin "8.17") (pinfunction "P8_17-GPIO_27_8.17") (pintype "passive"))
    )
    (net (code "90") (name "unconnected-(U2-P8_18-GPIO_65-Pad8.18)") (class "Default")
      (node (ref "U2") (pin "8.18") (pinfunction "P8_18-GPIO_65_8.18") (pintype "passive"))
    )
    (net (code "91") (name "unconnected-(U2-P8_20-MMC1_CMD-Pad8.20)") (class "Default")
      (node (ref "U2") (pin "8.20") (pinfunction "P8_20-MMC1_CMD_8.20") (pintype "passive"))
    )
    (net (code "92") (name "unconnected-(U2-P8_21-MMC1_CLK-Pad8.21)") (class "Default")
      (node (ref "U2") (pin "8.21") (pinfunction "P8_21-MMC1_CLK_8.21") (pintype "passive"))
    )
    (net (code "93") (name "unconnected-(U2-P8_22-MMC1_DAT5-Pad8.22)") (class "Default")
      (node (ref "U2") (pin "8.22") (pinfunction "P8_22-MMC1_DAT5_8.22") (pintype "passive"))
    )
    (net (code "94") (name "unconnected-(U2-P8_23-MMC1_DAT4-Pad8.23)") (class "Default")
      (node (ref "U2") (pin "8.23") (pinfunction "P8_23-MMC1_DAT4_8.23") (pintype "passive"))
    )
    (net (code "95") (name "unconnected-(U2-P8_24-MMC1_DAT1-Pad8.24)") (class "Default")
      (node (ref "U2") (pin "8.24") (pinfunction "P8_24-MMC1_DAT1_8.24") (pintype "passive"))
    )
    (net (code "96") (name "unconnected-(U2-P8_25-MMC1_DAT0-Pad8.25)") (class "Default")
      (node (ref "U2") (pin "8.25") (pinfunction "P8_25-MMC1_DAT0_8.25") (pintype "passive"))
    )
    (net (code "97") (name "unconnected-(U2-P8_27-LCD_VSYNC-Pad8.27)") (class "Default")
      (node (ref "U2") (pin "8.27") (pinfunction "P8_27-LCD_VSYNC_8.27") (pintype "passive"))
    )
    (net (code "98") (name "unconnected-(U2-P8_28-LCD_PCLK-Pad8.28)") (class "Default")
      (node (ref "U2") (pin "8.28") (pinfunction "P8_28-LCD_PCLK_8.28") (pintype "passive"))
    )
    (net (code "99") (name "unconnected-(U2-P8_29-LCD_HSYNC-Pad8.29)") (class "Default")
      (node (ref "U2") (pin "8.29") (pinfunction "P8_29-LCD_HSYNC_8.29") (pintype "passive"))
    )
    (net (code "100") (name "unconnected-(U2-P8_30-LCD_AC_BIAS-Pad8.30)") (class "Default")
      (node (ref "U2") (pin "8.30") (pinfunction "P8_30-LCD_AC_BIAS_8.30") (pintype "passive"))
    )
    (net (code "101") (name "unconnected-(U2-P8_31-LCD_DATA14-Pad8.31)") (class "Default")
      (node (ref "U2") (pin "8.31") (pinfunction "P8_31-LCD_DATA14_8.31") (pintype "passive"))
    )
    (net (code "102") (name "unconnected-(U2-P8_32-LCD_DATA15-Pad8.32)") (class "Default")
      (node (ref "U2") (pin "8.32") (pinfunction "P8_32-LCD_DATA15_8.32") (pintype "passive"))
    )
    (net (code "103") (name "unconnected-(U2-P8_33-LCD_DATA13-Pad8.33)") (class "Default")
      (node (ref "U2") (pin "8.33") (pinfunction "P8_33-LCD_DATA13_8.33") (pintype "passive"))
    )
    (net (code "104") (name "unconnected-(U2-P8_34-LCD_DATA11-Pad8.34)") (class "Default")
      (node (ref "U2") (pin "8.34") (pinfunction "P8_34-LCD_DATA11_8.34") (pintype "passive"))
    )
    (net (code "105") (name "unconnected-(U2-P8_35-LCD_DATA12-Pad8.35)") (class "Default")
      (node (ref "U2") (pin "8.35") (pinfunction "P8_35-LCD_DATA12_8.35") (pintype "passive"))
    )
    (net (code "106") (name "unconnected-(U2-P8_36-LCD_DATA10-Pad8.36)") (class "Default")
      (node (ref "U2") (pin "8.36") (pinfunction "P8_36-LCD_DATA10_8.36") (pintype "passive"))
    )
    (net (code "107") (name "unconnected-(U2-P8_37-LCD_DATA8-Pad8.37)") (class "Default")
      (node (ref "U2") (pin "8.37") (pinfunction "P8_37-LCD_DATA8_8.37") (pintype "passive"))
    )
    (net (code "108") (name "unconnected-(U2-P8_38-LCD_DATA9-Pad8.38)") (class "Default")
      (node (ref "U2") (pin "8.38") (pinfunction "P8_38-LCD_DATA9_8.38") (pintype "passive"))
    )
    (net (code "109") (name "unconnected-(U2-P8_39-LCD_DATA6-Pad8.39)") (class "Default")
      (node (ref "U2") (pin "8.39") (pinfunction "P8_39-LCD_DATA6_8.39") (pintype "passive"))
    )
    (net (code "110") (name "unconnected-(U2-P8_40-LCD_DATA7-Pad8.40)") (class "Default")
      (node (ref "U2") (pin "8.40") (pinfunction "P8_40-LCD_DATA7_8.40") (pintype "passive"))
    )
    (net (code "111") (name "unconnected-(U2-P8_41-LCD_DATA4-Pad8.41)") (class "Default")
      (node (ref "U2") (pin "8.41") (pinfunction "P8_41-LCD_DATA4_8.41") (pintype "passive"))
    )
    (net (code "112") (name "unconnected-(U2-P8_42-LCD_DATA5-Pad8.42)") (class "Default")
      (node (ref "U2") (pin "8.42") (pinfunction "P8_42-LCD_DATA5_8.42") (pintype "passive"))
    )
    (net (code "113") (name "unconnected-(U2-P8_43-LCD_DATA2-Pad8.43)") (class "Default")
      (node (ref "U2") (pin "8.43") (pinfunction "P8_43-LCD_DATA2_8.43") (pintype "passive"))
    )
    (net (code "114") (name "unconnected-(U2-P8_44-LCD_DATA3-Pad8.44)") (class "Default")
      (node (ref "U2") (pin "8.44") (pinfunction "P8_44-LCD_DATA3_8.44") (pintype "passive"))
    )
    (net (code "115") (name "unconnected-(U2-P8_45-LCD_DATA0-Pad8.45)") (class "Default")
      (node (ref "U2") (pin "8.45") (pinfunction "P8_45-LCD_DATA0_8.45") (pintype "passive"))
    )
    (net (code "116") (name "unconnected-(U2-P8_46-LCD_DATA1-Pad8.46)") (class "Default")
      (node (ref "U2") (pin "8.46") (pinfunction "P8_46-LCD_DATA1_8.46") (pintype "passive"))
    )
    (net (code "117") (name "unconnected-(U2-P9_8-SYS_5V-Pad9.8)") (class "Default")
      (node (ref "U2") (pin "9.8") (pinfunction "P9_8-SYS_5V_9.8") (pintype "passive"))
    )
    (net (code "118") (name "unconnected-(U2-P9_9-PWR_BUT-Pad9.9)") (class "Default")
      (node (ref "U2") (pin "9.9") (pinfunction "P9_9-PWR_BUT_9.9") (pintype "passive"))
    )
    (net (code "119") (name "unconnected-(U2-P9_10-SYS_RESETN-Pad9.10)") (class "Default")
      (node (ref "U2") (pin "9.10") (pinfunction "P9_10-SYS_RESETN_9.10") (pintype "passive"))
    )
    (net (code "120") (name "unconnected-(U2-P9_12-GPIO_60-Pad9.12)") (class "Default")
      (node (ref "U2") (pin "9.12") (pinfunction "P9_12-GPIO_60_9.12") (pintype "passive"))
    )
    (net (code "121") (name "unconnected-(U2-P9_14-EHRPWM1A-Pad9.14)") (class "Default")
      (node (ref "U2") (pin "9.14") (pinfunction "P9_14-EHRPWM1A_9.14") (pintype "passive"))
    )
    (net (code "122") (name "unconnected-(U2-P9_15-GPIO_48-Pad9.15)") (class "Default")
      (node (ref "U2") (pin "9.15") (pinfunction "P9_15-GPIO_48_9.15") (pintype "passive"))
    )
    (net (code "123") (name "unconnected-(U2-P9_16-EHRPWM1B-Pad9.16)") (class "Default")
      (node (ref "U2") (pin "9.16") (pinfunction "P9_16-EHRPWM1B_9.16") (pintype "passive"))
    )
    (net (code "124") (name "unconnected-(U2-P9_19-I2C2_SCL-Pad9.19)") (class "Default")
      (node (ref "U2") (pin "9.19") (pinfunction "P9_19-I2C2_SCL_9.19") (pintype "passive"))
    )
    (net (code "125") (name "unconnected-(U2-P9_20-I2C2_SDA-Pad9.20)") (class "Default")
      (node (ref "U2") (pin "9.20") (pinfunction "P9_20-I2C2_SDA_9.20") (pintype "passive"))
    )
    (net (code "126") (name "unconnected-(U2-P9_23-GPIO_49-Pad9.23)") (class "Default")
      (node (ref "U2") (pin "9.23") (pinfunction "P9_23-GPIO_49_9.23") (pintype "passive"))
    )
    (net (code "127") (name "unconnected-(U2-P9_25-GPIO_117-Pad9.25)") (class "Default")
      (node (ref "U2") (pin "9.25") (pinfunction "P9_25-GPIO_117_9.25") (pintype "passive"))
    )
    (net (code "128") (name "unconnected-(U2-P9_27-GPIO_115-Pad9.27)") (class "Default")
      (node (ref "U2") (pin "9.27") (pinfunction "P9_27-GPIO_115_9.27") (pintype "passive"))
    )
    (net (code "129") (name "unconnected-(U2-P9_28-SPI1_CS0-Pad9.28)") (class "Default")
      (node (ref "U2") (pin "9.28") (pinfunction "P9_28-SPI1_CS0_9.28") (pintype "passive"))
    )
    (net (code "130") (name "unconnected-(U2-P9_29-SPI1_D0-Pad9.29)") (class "Default")
      (node (ref "U2") (pin "9.29") (pinfunction "P9_29-SPI1_D0_9.29") (pintype "passive"))
    )
    (net (code "131") (name "unconnected-(U2-P9_30-GPIO_112-Pad9.30)") (class "Default")
      (node (ref "U2") (pin "9.30") (pinfunction "P9_30-GPIO_112_9.30") (pintype "passive"))
    )
    (net (code "132") (name "unconnected-(U2-P9_31-SPI1_SCLK-Pad9.31)") (class "Default")
      (node (ref "U2") (pin "9.31") (pinfunction "P9_31-SPI1_SCLK_9.31") (pintype "passive"))
    )
    (net (code "133") (name "unconnected-(U2-P9_32-VDD_ADC-Pad9.32)") (class "Default")
      (node (ref "U2") (pin "9.32") (pinfunction "P9_32-VDD_ADC_9.32") (pintype "passive"))
    )
    (net (code "134") (name "unconnected-(U2-P9_33-AIN4-Pad9.33)") (class "Default")
      (node (ref "U2") (pin "9.33") (pinfunction "P9_33-AIN4_9.33") (pintype "passive"))
    )
    (net (code "135") (name "unconnected-(U2-P9_34-GNDA_ADC-Pad9.34)") (class "Default")
      (node (ref "U2") (pin "9.34") (pinfunction "P9_34-GNDA_ADC_9.34") (pintype "passive"))
    )
    (net (code "136") (name "unconnected-(U2-P9_35-AIN6-Pad9.35)") (class "Default")
      (node (ref "U2") (pin "9.35") (pinfunction "P9_35-AIN6_9.35") (pintype "passive"))
    )
    (net (code "137") (name "unconnected-(U2-P9_36-AIN5-Pad9.36)") (class "Default")
      (node (ref "U2") (pin "9.36") (pinfunction "P9_36-AIN5_9.36") (pintype "passive"))
    )
    (net (code "138") (name "unconnected-(U2-P9_37-AIN2-Pad9.37)") (class "Default")
      (node (ref "U2") (pin "9.37") (pinfunction "P9_37-AIN2_9.37") (pintype "passive"))
    )
    (net (code "139") (name "unconnected-(U2-P9_38-AIN3-Pad9.38)") (class "Default")
      (node (ref "U2") (pin "9.38") (pinfunction "P9_38-AIN3_9.38") (pintype "passive"))
    )
    (net (code "140") (name "unconnected-(U2-P9_40-AIN1-Pad9.40)") (class "Default")
      (node (ref "U2") (pin "9.40") (pinfunction "P9_40-AIN1_9.40") (pintype "passive"))
    )
    (net (code "141") (name "unconnected-(U2-P9_41-GPIO_20-Pad9.41)") (class "Default")
      (node (ref "U2") (pin "9.41") (pinfunction "P9_41-GPIO_20_9.41") (pintype "input"))
    )
    (net (code "142") (name "unconnected-(U2-P9_42-ECAPPWM0-Pad9.42)") (class "Default")
      (node (ref "U2") (pin "9.42") (pinfunction "P9_42-ECAPPWM0_9.42") (pintype "passive"))
    )
    (net (code "143") (name "unconnected-(U4-P1.0-Pad2)") (class "Default")
      (node (ref "U4") (pin "2") (pinfunction "P1.0_2") (pintype "bidirectional"))
    )
    (net (code "144") (name "unconnected-(U4-P1.3-Pad5)") (class "Default")
      (node (ref "U4") (pin "5") (pinfunction "P1.3_5") (pintype "bidirectional"))
    )
    (net (code "145") (name "unconnected-(U4-P1.4-Pad6)") (class "Default")
      (node (ref "U4") (pin "6") (pinfunction "P1.4_6") (pintype "bidirectional"))
    )
    (net (code "146") (name "unconnected-(U4-P2.1-Pad11)") (class "Default")
      (node (ref "U4") (pin "11") (pinfunction "P2.1_11") (pintype "bidirectional"))
    )
  )
)
